# LM317_PSU.net
KiCad netlist of a schematic drawn in EAGLE
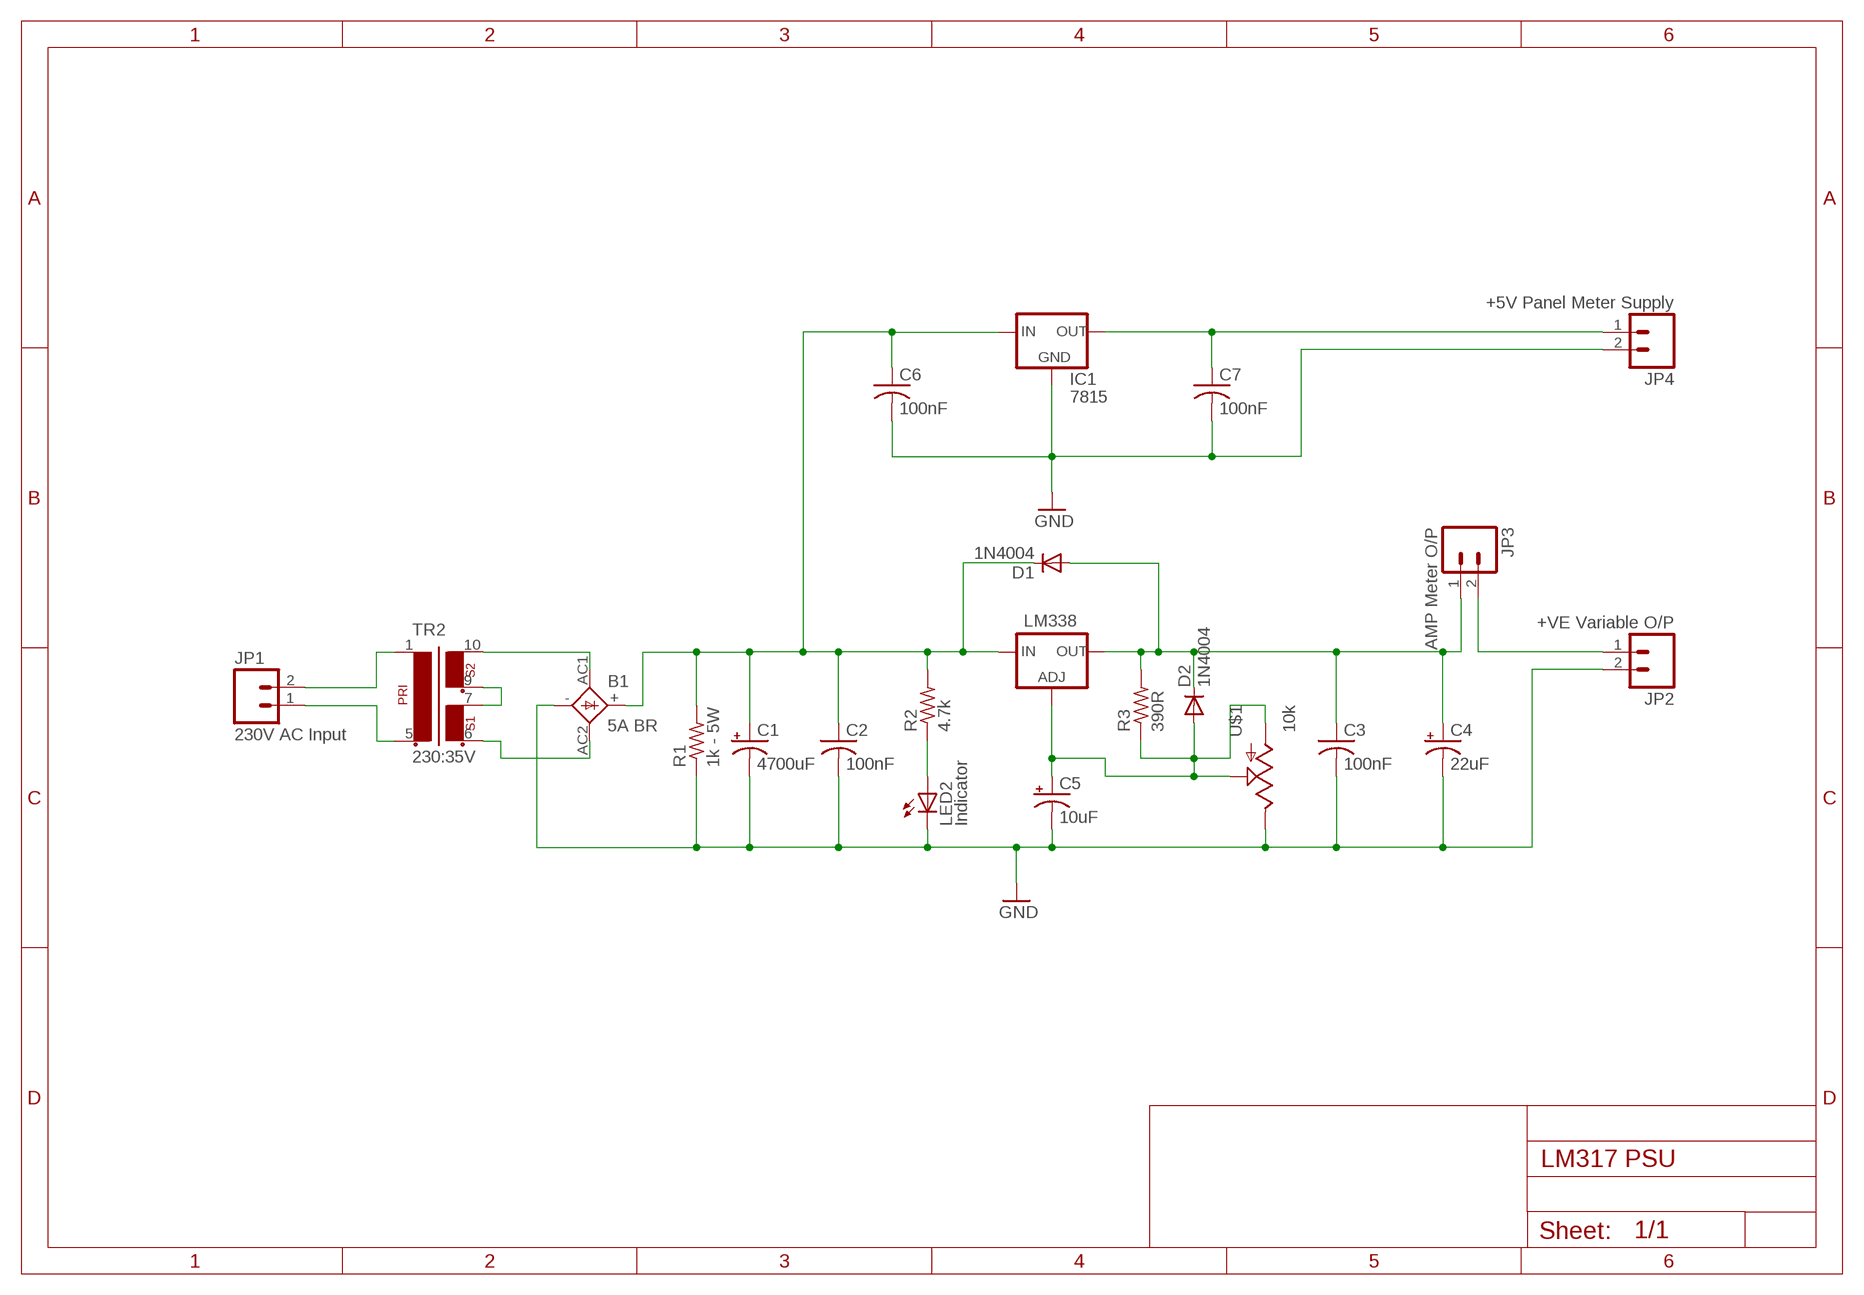
[diagram p0: schematic, sheet 1]

(export (version "E")
  (design (tool "Eeschema 10.0.6"))
  (components
    (comp (ref "B1")
      (value "5A BR")
      (footprint "eagle-import:GBPC80X")
      (libsource (lib "eagle-import") (part "GBPC80X"))
    )
    (comp (ref "C1")
      (value "4700uF")
      (footprint "eagle-import:E7,5-16")
      (libsource (lib "eagle-import") (part "CPOL-USE7.5-16"))
    )
    (comp (ref "C2")
      (value "100nF")
      (footprint "eagle-import:C025-040X050")
      (libsource (lib "eagle-import") (part "C-US025-040X050"))
    )
    (comp (ref "C3")
      (value "100nF")
      (footprint "eagle-import:C025-040X050")
      (libsource (lib "eagle-import") (part "C-US025-040X050"))
    )
    (comp (ref "C4")
      (value "22uF")
      (footprint "eagle-import:E5-6")
      (libsource (lib "eagle-import") (part "CPOL-USE5-6"))
    )
    (comp (ref "C5")
      (value "10uF")
      (footprint "eagle-import:E5-6")
      (libsource (lib "eagle-import") (part "CPOL-USE5-6"))
    )
    (comp (ref "C6")
      (value "100nF")
      (footprint "eagle-import:C025-040X050")
      (libsource (lib "eagle-import") (part "C-US025-040X050"))
    )
    (comp (ref "C7")
      (value "100nF")
      (footprint "eagle-import:C025-040X050")
      (libsource (lib "eagle-import") (part "C-US025-040X050"))
    )
    (comp (ref "D1")
      (value "1N4004")
      (footprint "eagle-import:DO41-10")
      (libsource (lib "eagle-import") (part "1N4004"))
    )
    (comp (ref "D2")
      (value "1N4004")
      (footprint "eagle-import:DO41-10")
      (libsource (lib "eagle-import") (part "1N4004"))
    )
    (comp (ref "IC1")
      (value "7815")
      (footprint "eagle-import:TO220-IGO")
      (libsource (lib "eagle-import") (part "V_REG_78XXSINK"))
    )
    (comp (ref "JP1")
      (value "230V AC Input")
      (footprint "eagle-import:SCREWTERMINAL-5MM-2")
      (libsource (lib "eagle-import") (part "M025MM"))
    )
    (comp (ref "JP2")
      (value "+VE Variable O/P")
      (footprint "eagle-import:SCREWTERMINAL-5MM-2")
      (libsource (lib "eagle-import") (part "M025MM"))
    )
    (comp (ref "JP3")
      (value "AMP Meter O/P")
      (footprint "eagle-import:SCREWTERMINAL-5MM-2")
      (libsource (lib "eagle-import") (part "M025MM"))
    )
    (comp (ref "JP4")
      (value "+5V Panel Meter Supply")
      (footprint "eagle-import:SCREWTERMINAL-5MM-2")
      (libsource (lib "eagle-import") (part "M025MM"))
    )
    (comp (ref "LED2")
      (value "Indicator")
      (footprint "eagle-import:LED5MM")
      (libsource (lib "eagle-import") (part "LED5MM"))
    )
    (comp (ref "LM338")
      (value "V_REG_317SINK")
      (footprint "eagle-import:TO220-ADJ")
      (libsource (lib "eagle-import") (part "V_REG_317SINK"))
    )
    (comp (ref "R1")
      (value "1k - 5W")
      (footprint "eagle-import:V234_12")
      (libsource (lib "eagle-import") (part "R-US_V234/12"))
    )
    (comp (ref "R2")
      (value "4.7k")
      (footprint "eagle-import:0805-THM")
      (libsource (lib "eagle-import") (part "R-US_FLIPFLOP"))
    )
    (comp (ref "R3")
      (value "390R")
      (footprint "eagle-import:0805-THM")
      (libsource (lib "eagle-import") (part "R-US_FLIPFLOP"))
    )
    (comp (ref "TR2")
      (value "230:35V")
      (footprint "eagle-import:EI42-2")
      (libsource (lib "eagle-import") (part "EI42-2"))
    )
    (comp (ref "U$1")
      (value "10k")
      (footprint "eagle-import:POT_ALPHA_RV16AF-20")
      (libsource (lib "eagle-import") (part "POT-RV16AF-20"))
    )
  )
  (nets
    (net (code "1") (name "GND") (class "Default")
      (node (ref "B1") (pin "-") (pinfunction "-_-") (pintype "passive"))
      (node (ref "C1") (pin "-") (pinfunction "-_-") (pintype "passive"))
      (node (ref "C2") (pin "2") (pinfunction "2_2") (pintype "passive"))
      (node (ref "C3") (pin "2") (pinfunction "2_2") (pintype "passive"))
      (node (ref "C4") (pin "-") (pinfunction "-_-") (pintype "passive"))
      (node (ref "C5") (pin "-") (pinfunction "-_-") (pintype "passive"))
      (node (ref "C6") (pin "2") (pinfunction "2_2") (pintype "passive"))
      (node (ref "C7") (pin "2") (pinfunction "2_2") (pintype "passive"))
      (node (ref "IC1") (pin "GND") (pinfunction "GND_GND") (pintype "input"))
      (node (ref "JP2") (pin "2") (pinfunction "2_2") (pintype "passive"))
      (node (ref "JP4") (pin "2") (pinfunction "2_2") (pintype "passive"))
      (node (ref "LED2") (pin "K") (pinfunction "C_K") (pintype "passive"))
      (node (ref "R1") (pin "1") (pinfunction "1_1") (pintype "passive"))
      (node (ref "U$1") (pin "3") (pinfunction "E_3") (pintype "passive"))
    )
    (net (code "2") (name "Net-(B1-Pad+)") (class "Default")
      (node (ref "B1") (pin "+") (pinfunction "+_+") (pintype "passive"))
      (node (ref "C1") (pin "+") (pinfunction "+_+") (pintype "passive"))
      (node (ref "C2") (pin "1") (pinfunction "1_1") (pintype "passive"))
      (node (ref "C6") (pin "1") (pinfunction "1_1") (pintype "passive"))
      (node (ref "D1") (pin "C") (pinfunction "C_C") (pintype "passive"))
      (node (ref "IC1") (pin "IN") (pinfunction "IN_IN") (pintype "input"))
      (node (ref "LM338") (pin "IN") (pinfunction "IN_IN") (pintype "input"))
      (node (ref "R1") (pin "2") (pinfunction "2_2") (pintype "passive"))
      (node (ref "R2") (pin "2") (pinfunction "2_2") (pintype "passive"))
    )
    (net (code "3") (name "Net-(C3-Pad1)") (class "Default")
      (node (ref "C3") (pin "1") (pinfunction "1_1") (pintype "passive"))
      (node (ref "C4") (pin "+") (pinfunction "+_+") (pintype "passive"))
      (node (ref "D1") (pin "A") (pinfunction "A_A") (pintype "passive"))
      (node (ref "D2") (pin "C") (pinfunction "C_C") (pintype "passive"))
      (node (ref "JP3") (pin "1") (pinfunction "1_1") (pintype "passive"))
      (node (ref "LM338") (pin "OUT") (pinfunction "OUT_OUT") (pintype "output"))
      (node (ref "R3") (pin "2") (pinfunction "2_2") (pintype "passive"))
    )
    (net (code "4") (name "Net-(C7-Pad1)") (class "Default")
      (node (ref "C7") (pin "1") (pinfunction "1_1") (pintype "passive"))
      (node (ref "IC1") (pin "OUT") (pinfunction "OUT_OUT") (pintype "output"))
      (node (ref "JP4") (pin "1") (pinfunction "1_1") (pintype "passive"))
    )
    (net (code "5") (name "Net-(JP1-Pad2)") (class "Default")
      (node (ref "JP1") (pin "2") (pinfunction "2_2") (pintype "passive"))
      (node (ref "TR2") (pin "1") (pinfunction "1_1") (pintype "passive"))
    )
    (net (code "6") (name "Net-(JP2-Pad1)") (class "Default")
      (node (ref "JP2") (pin "1") (pinfunction "1_1") (pintype "passive"))
      (node (ref "JP3") (pin "2") (pinfunction "2_2") (pintype "passive"))
    )
    (net (code "7") (name "Net-(LED2-PadA)") (class "Default")
      (node (ref "LED2") (pin "A") (pinfunction "A_A") (pintype "passive"))
      (node (ref "R2") (pin "1") (pinfunction "1_1") (pintype "passive"))
    )
    (net (code "8") (name "Net-(TR2-2)") (class "Default")
      (node (ref "JP1") (pin "1") (pinfunction "1_1") (pintype "passive"))
      (node (ref "TR2") (pin "5") (pinfunction "2_5") (pintype "passive"))
    )
    (net (code "9") (name "Net-(TR2-3)") (class "Default")
      (node (ref "B1") (pin "AC2") (pinfunction "AC2_AC2") (pintype "passive"))
      (node (ref "TR2") (pin "6") (pinfunction "3_6") (pintype "passive"))
    )
    (net (code "10") (name "Net-(TR2-4)") (class "Default")
      (node (ref "TR2") (pin "7") (pinfunction "4_7") (pintype "passive"))
      (node (ref "TR2") (pin "9") (pinfunction "5_9") (pintype "passive"))
    )
    (net (code "11") (name "Net-(TR2-6)") (class "Default")
      (node (ref "B1") (pin "AC1") (pinfunction "AC1_AC1") (pintype "passive"))
      (node (ref "TR2") (pin "10") (pinfunction "6_10") (pintype "passive"))
    )
    (net (code "12") (name "Net-(U$1-A)") (class "Default")
      (node (ref "C5") (pin "+") (pinfunction "+_+") (pintype "passive"))
      (node (ref "D2") (pin "A") (pinfunction "A_A") (pintype "passive"))
      (node (ref "LM338") (pin "ADJ") (pinfunction "ADJ_ADJ") (pintype "input"))
      (node (ref "R3") (pin "1") (pinfunction "1_1") (pintype "passive"))
      (node (ref "U$1") (pin "1") (pinfunction "A_1") (pintype "passive"))
      (node (ref "U$1") (pin "2") (pinfunction "S_2") (pintype "passive"))
    )
  )
)
